# LiPo-Rechargable-ESP2866.net
KiCad netlist of a schematic drawn in EAGLE
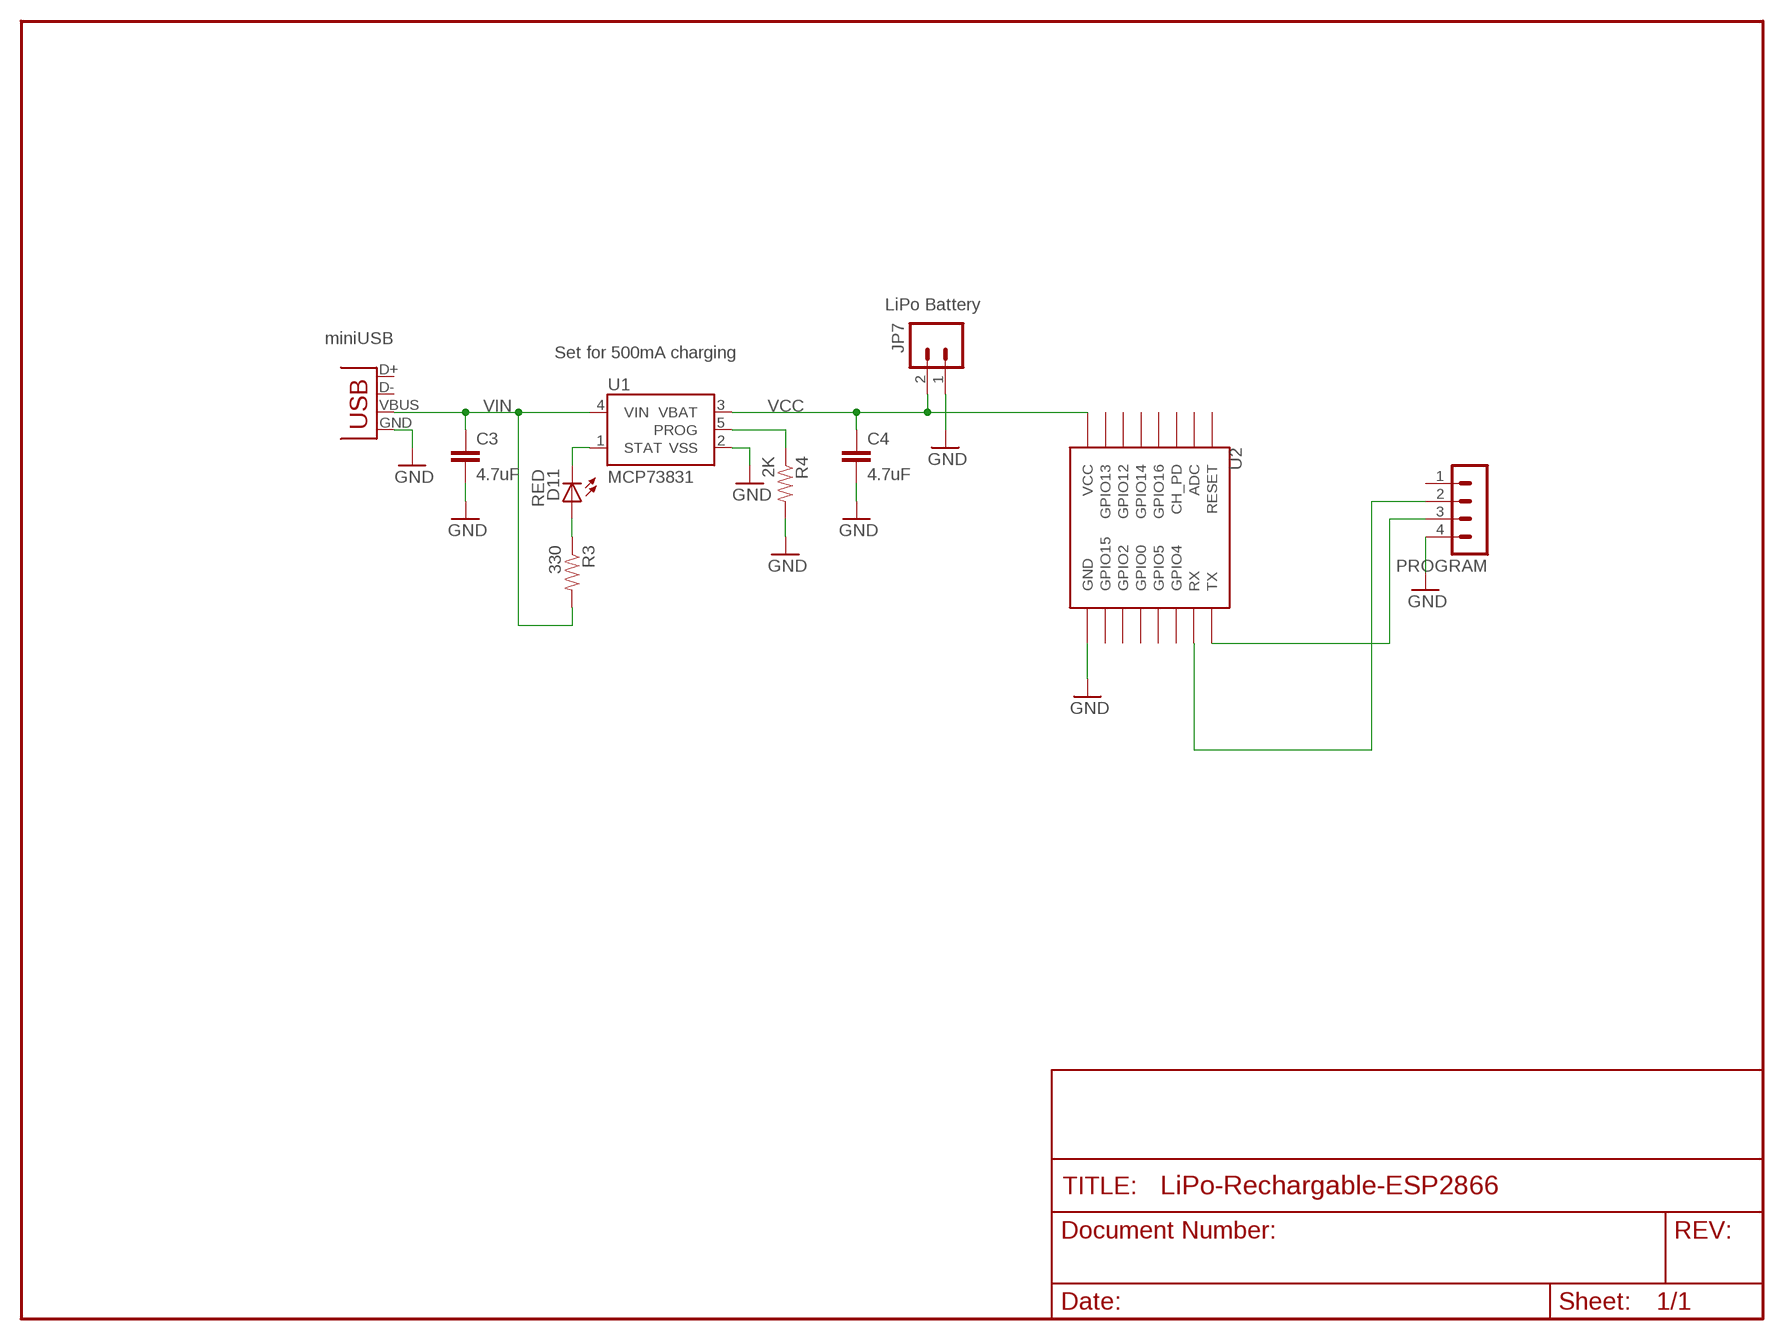
[diagram p0: schematic, sheet 1]

(export (version "E")
  (design (tool "Eeschema 10.0.6"))
  (components
    (comp (ref "C3")
      (value "4.7uF")
      (footprint "eagle-import:0402-CAP")
      (libsource (lib "eagle-import") (part "CAP0402-CAP"))
    )
    (comp (ref "C4")
      (value "4.7uF")
      (footprint "eagle-import:0402-CAP")
      (libsource (lib "eagle-import") (part "CAP0402-CAP"))
    )
    (comp (ref "D11")
      (value "RED")
      (footprint "eagle-import:LED-0603")
      (libsource (lib "eagle-import") (part "LED0603"))
    )
    (comp (ref "JP7")
      (value "LiPo Battery")
      (footprint "eagle-import:JST-2-SMD")
      (libsource (lib "eagle-import") (part "M02-JST-2MM-SMT"))
    )
    (comp (ref "PROGRAM")
      (value "MA04-1")
      (footprint "eagle-import:MA04-1")
      (libsource (lib "eagle-import") (part "MA04-1"))
    )
    (comp (ref "R3")
      (value "330")
      (footprint "eagle-import:0402-RES")
      (libsource (lib "eagle-import") (part "RESISTOR0402-RES"))
    )
    (comp (ref "R4")
      (value "2K")
      (footprint "eagle-import:0402-RES")
      (libsource (lib "eagle-import") (part "RESISTOR0402-RES"))
    )
    (comp (ref "U1")
      (value "MCP73831")
      (footprint "eagle-import:SOT23-5")
      (libsource (lib "eagle-import") (part "MCP73831"))
    )
    (comp (ref "U2")
      (value "ESP12")
      (footprint "eagle-import:ESP12")
      (libsource (lib "eagle-import") (part "ESP12"))
    )
    (comp (ref "X1")
      (value "Micro USB")
      (footprint "eagle-import:USB-MINIB")
      (libsource (lib "eagle-import") (part "USBSMD"))
    )
  )
  (nets
    (net (code "1") (name "/VCC") (class "Default")
      (node (ref "C4") (pin "1") (pinfunction "1_1") (pintype "passive"))
      (node (ref "JP7") (pin "2") (pinfunction "2_2") (pintype "passive"))
      (node (ref "U1") (pin "3") (pinfunction "VBAT_3") (pintype "power_in"))
      (node (ref "U2") (pin "VCC") (pinfunction "VCC_VCC") (pintype "bidirectional"))
    )
    (net (code "2") (name "/VIN") (class "Default")
      (node (ref "C3") (pin "1") (pinfunction "1_1") (pintype "passive"))
      (node (ref "R3") (pin "2") (pinfunction "2_2") (pintype "passive"))
      (node (ref "U1") (pin "4") (pinfunction "VIN_4") (pintype "power_in"))
      (node (ref "X1") (pin "VBUS") (pinfunction "VBUS_VBUS") (pintype "bidirectional"))
    )
    (net (code "3") (name "GND") (class "Default")
      (node (ref "C3") (pin "2") (pinfunction "2_2") (pintype "passive"))
      (node (ref "C4") (pin "2") (pinfunction "2_2") (pintype "passive"))
      (node (ref "JP7") (pin "1") (pinfunction "1_1") (pintype "passive"))
      (node (ref "PROGRAM") (pin "4") (pinfunction "4_4") (pintype "passive"))
      (node (ref "R4") (pin "2") (pinfunction "2_2") (pintype "passive"))
      (node (ref "U1") (pin "2") (pinfunction "VSS_2") (pintype "power_in"))
      (node (ref "U2") (pin "GND") (pinfunction "GND_GND") (pintype "bidirectional"))
      (node (ref "X1") (pin "GND") (pinfunction "GND_GND") (pintype "bidirectional"))
    )
    (net (code "4") (name "Net-(D11-PadA)") (class "Default")
      (node (ref "D11") (pin "A") (pinfunction "A_A") (pintype "passive"))
      (node (ref "R3") (pin "1") (pinfunction "1_1") (pintype "passive"))
    )
    (net (code "5") (name "Net-(PROGRAM-Pad2)") (class "Default")
      (node (ref "PROGRAM") (pin "2") (pinfunction "2_2") (pintype "passive"))
      (node (ref "U2") (pin "RX") (pinfunction "RX_RX") (pintype "bidirectional"))
    )
    (net (code "6") (name "Net-(PROGRAM-Pad3)") (class "Default")
      (node (ref "PROGRAM") (pin "3") (pinfunction "3_3") (pintype "passive"))
      (node (ref "U2") (pin "TX") (pinfunction "TX_TX") (pintype "bidirectional"))
    )
    (net (code "7") (name "Net-(U1-PROG)") (class "Default")
      (node (ref "R4") (pin "1") (pinfunction "1_1") (pintype "passive"))
      (node (ref "U1") (pin "5") (pinfunction "PROG_5") (pintype "input"))
    )
    (net (code "8") (name "Net-(U1-STAT)") (class "Default")
      (node (ref "D11") (pin "C") (pinfunction "C_C") (pintype "passive"))
      (node (ref "U1") (pin "1") (pinfunction "STAT_1") (pintype "output"))
    )
    (net (code "9") (name "unconnected-(PROGRAM-Pad1)") (class "Default")
      (node (ref "PROGRAM") (pin "1") (pinfunction "1_1") (pintype "passive"))
    )
    (net (code "10") (name "unconnected-(U2-PadADC)") (class "Default")
      (node (ref "U2") (pin "ADC") (pinfunction "ADC_ADC") (pintype "bidirectional"))
    )
    (net (code "11") (name "unconnected-(U2-PadCH_PD)") (class "Default")
      (node (ref "U2") (pin "CH_PD") (pinfunction "CH_PD_CH_PD") (pintype "bidirectional"))
    )
    (net (code "12") (name "unconnected-(U2-PadGPIO0)") (class "Default")
      (node (ref "U2") (pin "GPIO0") (pinfunction "GPIO0_GPIO0") (pintype "bidirectional"))
    )
    (net (code "13") (name "unconnected-(U2-PadGPIO2)") (class "Default")
      (node (ref "U2") (pin "GPIO2") (pinfunction "GPIO2_GPIO2") (pintype "bidirectional"))
    )
    (net (code "14") (name "unconnected-(U2-PadGPIO4)") (class "Default")
      (node (ref "U2") (pin "GPIO4") (pinfunction "GPIO4_GPIO4") (pintype "bidirectional"))
    )
    (net (code "15") (name "unconnected-(U2-PadGPIO5)") (class "Default")
      (node (ref "U2") (pin "GPIO5") (pinfunction "GPIO5_GPIO5") (pintype "bidirectional"))
    )
    (net (code "16") (name "unconnected-(U2-PadGPIO12)") (class "Default")
      (node (ref "U2") (pin "GPIO12") (pinfunction "GPIO12_GPIO12") (pintype "bidirectional"))
    )
    (net (code "17") (name "unconnected-(U2-PadGPIO13)") (class "Default")
      (node (ref "U2") (pin "GPIO13") (pinfunction "GPIO13_GPIO13") (pintype "bidirectional"))
    )
    (net (code "18") (name "unconnected-(U2-PadGPIO14)") (class "Default")
      (node (ref "U2") (pin "GPIO14") (pinfunction "GPIO14_GPIO14") (pintype "bidirectional"))
    )
    (net (code "19") (name "unconnected-(U2-PadGPIO15)") (class "Default")
      (node (ref "U2") (pin "GPIO15") (pinfunction "GPIO15_GPIO15") (pintype "bidirectional"))
    )
    (net (code "20") (name "unconnected-(U2-PadGPIO16)") (class "Default")
      (node (ref "U2") (pin "GPIO16") (pinfunction "GPIO16_GPIO16") (pintype "bidirectional"))
    )
    (net (code "21") (name "unconnected-(U2-PadRESET)") (class "Default")
      (node (ref "U2") (pin "RESET") (pinfunction "RESET_RESET") (pintype "bidirectional"))
    )
    (net (code "22") (name "unconnected-(X1-PadD+)") (class "Default")
      (node (ref "X1") (pin "D+") (pinfunction "D+_D+") (pintype "bidirectional"))
    )
    (net (code "23") (name "unconnected-(X1-PadD-)") (class "Default")
      (node (ref "X1") (pin "D-") (pinfunction "D-_D-") (pintype "bidirectional"))
    )
  )
)
